# Mosfet_Board.net
KiCad netlist of a schematic drawn in EAGLE
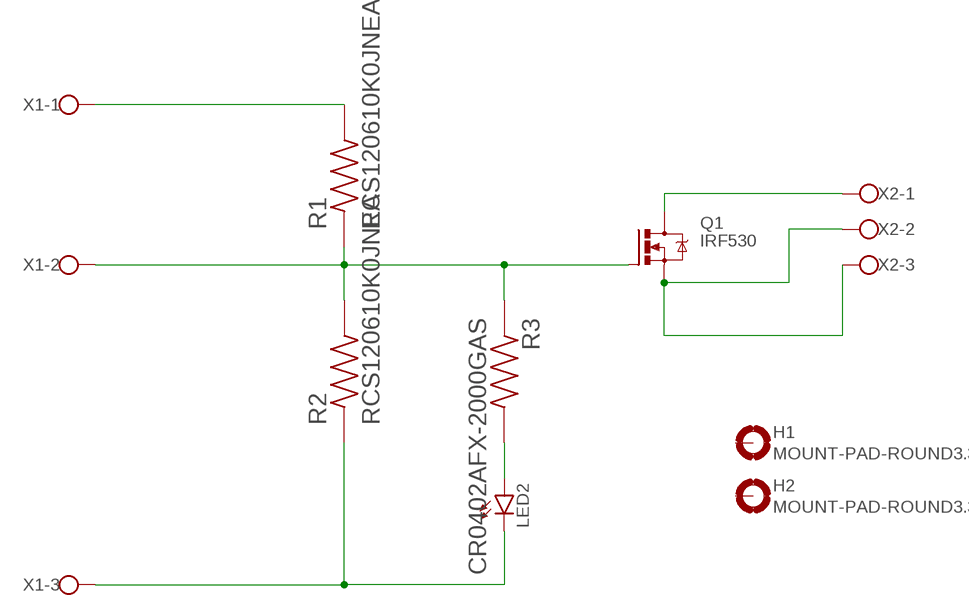
[diagram p0: schematic, sheet 1]

(export (version "E")
  (design (tool "Eeschema 10.0.6"))
  (components
    (comp (ref "H1")
      (value "MOUNT-PAD-ROUND3.3")
      (footprint "eagle-import:3,3-PAD")
      (libsource (lib "eagle-import") (part "MOUNT-PAD-ROUND3.3"))
    )
    (comp (ref "H2")
      (value "MOUNT-PAD-ROUND3.3")
      (footprint "eagle-import:3,3-PAD")
      (libsource (lib "eagle-import") (part "MOUNT-PAD-ROUND3.3"))
    )
    (comp (ref "LED2")
      (value "LED")
      (footprint "eagle-import:SMARTLED-TTW")
      (libsource (lib "eagle-import") (part "LED"))
    )
    (comp (ref "Q1")
      (value "IRF530")
      (footprint "eagle-import:TO220BV")
      (libsource (lib "eagle-import") (part "IRF530"))
    )
    (comp (ref "R1")
      (value "RCS120610K0JNEA")
      (footprint "eagle-import:RESC3116X65N")
      (fields (field (name "MF") "Vishay"))
      (libsource (lib "eagle-import") (part "RCS120610K0JNEA"))
    )
    (comp (ref "R2")
      (value "RCS120610K0JNEA")
      (footprint "eagle-import:RESC3116X65N")
      (fields (field (name "MF") "Vishay"))
      (libsource (lib "eagle-import") (part "RCS120610K0JNEA"))
    )
    (comp (ref "R3")
      (value "CR0402AFX-2000GAS")
      (footprint "eagle-import:RESC1005X37N")
      (fields (field (name "MF") "Bourns"))
      (libsource (lib "eagle-import") (part "CR0402AFX-2000GAS"))
    )
    (comp (ref "X1")
      (value "W237-103")
      (footprint "eagle-import:W237-103")
      (fields (field (name "MPN") "237-103"))
      (libsource (lib "eagle-import") (part "W237-103"))
    )
    (comp (ref "X2")
      (value "W237-103")
      (footprint "eagle-import:W237-103")
      (fields (field (name "MPN") "237-103"))
      (libsource (lib "eagle-import") (part "W237-103"))
    )
  )
  (nets
    (net (code "1") (name "Net-(LED2-A)") (class "Default")
      (node (ref "LED2") (pin "A@1") (pinfunction "A_A@1") (pintype "passive"))
      (node (ref "R3") (pin "2") (pinfunction "2_2") (pintype "passive"))
    )
    (net (code "2") (name "Net-(LED2-C)") (class "Default")
      (node (ref "LED2") (pin "C@1") (pinfunction "C_C@1") (pintype "passive"))
      (node (ref "R2") (pin "1") (pinfunction "1_1") (pintype "passive"))
      (node (ref "X1") (pin "3") (pinfunction "KL_3") (pintype "passive"))
    )
    (net (code "3") (name "Net-(X1A-KL)") (class "Default")
      (node (ref "R1") (pin "2") (pinfunction "2_2") (pintype "passive"))
      (node (ref "X1") (pin "1") (pinfunction "KL_1") (pintype "passive"))
    )
    (net (code "4") (name "Net-(X1B-KL)") (class "Default")
      (node (ref "Q1") (pin "G") (pinfunction "G_G") (pintype "passive"))
      (node (ref "R1") (pin "1") (pinfunction "1_1") (pintype "passive"))
      (node (ref "R2") (pin "2") (pinfunction "2_2") (pintype "passive"))
      (node (ref "R3") (pin "1") (pinfunction "1_1") (pintype "passive"))
      (node (ref "X1") (pin "2") (pinfunction "KL_2") (pintype "passive"))
    )
    (net (code "5") (name "Net-(X2A-KL)") (class "Default")
      (node (ref "Q1") (pin "D") (pinfunction "D_D") (pintype "passive"))
      (node (ref "X2") (pin "1") (pinfunction "KL_1") (pintype "passive"))
    )
    (net (code "6") (name "Net-(X2B-KL)") (class "Default")
      (node (ref "Q1") (pin "S") (pinfunction "S_S") (pintype "passive"))
      (node (ref "X2") (pin "2") (pinfunction "KL_2") (pintype "passive"))
      (node (ref "X2") (pin "3") (pinfunction "KL_3") (pintype "passive"))
    )
    (net (code "7") (name "unconnected-(H1-MOUNT-PadB3,3)") (class "Default")
      (node (ref "H1") (pin "B3,3") (pinfunction "MOUNT_B3,3") (pintype "passive"))
    )
    (net (code "8") (name "unconnected-(H2-MOUNT-PadB3,3)") (class "Default")
      (node (ref "H2") (pin "B3,3") (pinfunction "MOUNT_B3,3") (pintype "passive"))
    )
  )
)
